# Sensors.net
KiCad netlist of a schematic drawn in Altium Designer
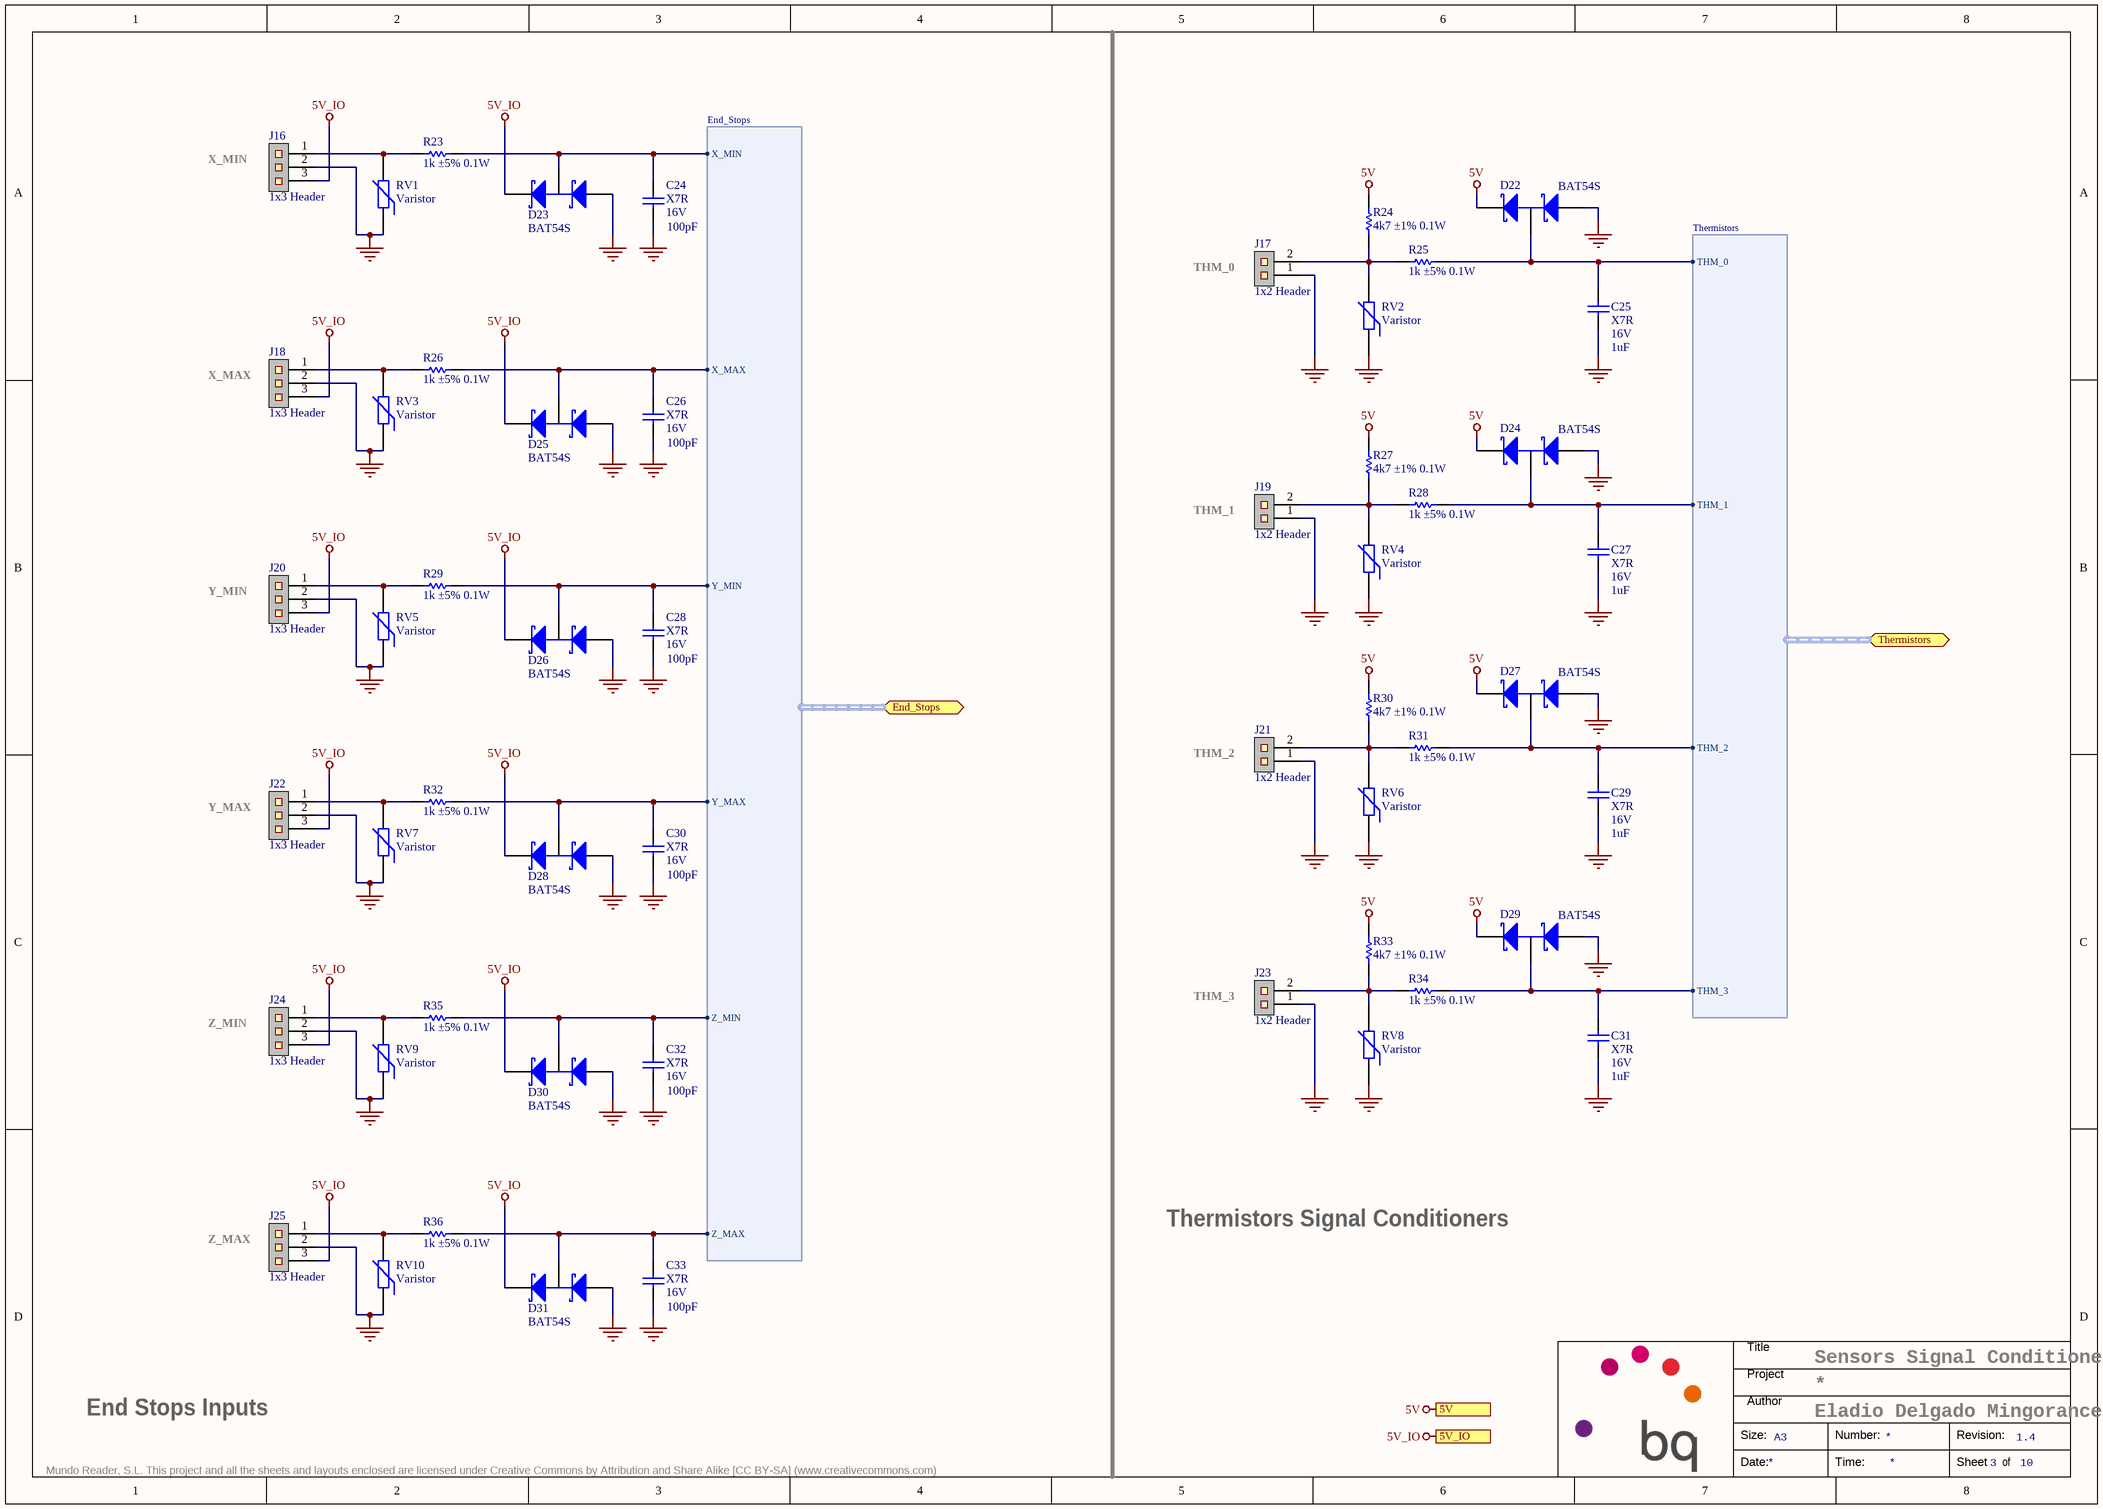
[diagram p0: Sensors.SchDoc]

(export (version "E")
  (design (tool "Eeschema 10.0.6"))
  (components
    (comp (ref "C24")
      (value "Capacitor")
      (footprint "C0603")
      (fields
        (field (name "DIELECTRIC") "X7R")
        (field (name "VOLTAGE") "16V")
        (field (name "CAPACITANCE") "100pF")
        (field (name "PART NUMBER") "C0603_100pF_16V_±10%")
        (field (name "TOLERANCE") "±10%")
        (field (name "MANUFACTURER") "Kemet")
      )
      (libsource (lib "Pasives_Capacitor_SMD") (part "Capacitor"))
    )
    (comp (ref "C25")
      (value "Capacitor")
      (footprint "C0603")
      (fields
        (field (name "DIELECTRIC") "X7R")
        (field (name "VOLTAGE") "16V")
        (field (name "CAPACITANCE") "1uF")
        (field (name "PART NUMBER") "C0603_1uF_16V_±10%_X7R")
        (field (name "TOLERANCE") "±10%")
        (field (name "MANUFACTURER") "TDK")
      )
      (libsource (lib "Pasives_Capacitor_SMD") (part "Capacitor"))
    )
    (comp (ref "C26")
      (value "Capacitor")
      (footprint "C0603")
      (fields
        (field (name "DIELECTRIC") "X7R")
        (field (name "VOLTAGE") "16V")
        (field (name "CAPACITANCE") "100pF")
        (field (name "PART NUMBER") "C0603_100pF_16V_±10%")
        (field (name "TOLERANCE") "±10%")
        (field (name "MANUFACTURER") "Kemet")
      )
      (libsource (lib "Pasives_Capacitor_SMD") (part "Capacitor"))
    )
    (comp (ref "C27")
      (value "Capacitor")
      (footprint "C0603")
      (fields
        (field (name "DIELECTRIC") "X7R")
        (field (name "VOLTAGE") "16V")
        (field (name "CAPACITANCE") "1uF")
        (field (name "PART NUMBER") "C0603_1uF_16V_±10%_X7R")
        (field (name "TOLERANCE") "±10%")
        (field (name "MANUFACTURER") "TDK")
      )
      (libsource (lib "Pasives_Capacitor_SMD") (part "Capacitor"))
    )
    (comp (ref "C28")
      (value "Capacitor")
      (footprint "C0603")
      (fields
        (field (name "DIELECTRIC") "X7R")
        (field (name "VOLTAGE") "16V")
        (field (name "CAPACITANCE") "100pF")
        (field (name "PART NUMBER") "C0603_100pF_16V_±10%")
        (field (name "TOLERANCE") "±10%")
        (field (name "MANUFACTURER") "Kemet")
      )
      (libsource (lib "Pasives_Capacitor_SMD") (part "Capacitor"))
    )
    (comp (ref "C29")
      (value "Capacitor")
      (footprint "C0603")
      (fields
        (field (name "DIELECTRIC") "X7R")
        (field (name "VOLTAGE") "16V")
        (field (name "CAPACITANCE") "1uF")
        (field (name "PART NUMBER") "C0603_1uF_16V_±10%_X7R")
        (field (name "TOLERANCE") "±10%")
        (field (name "MANUFACTURER") "TDK")
      )
      (libsource (lib "Pasives_Capacitor_SMD") (part "Capacitor"))
    )
    (comp (ref "C30")
      (value "Capacitor")
      (footprint "C0603")
      (fields
        (field (name "DIELECTRIC") "X7R")
        (field (name "VOLTAGE") "16V")
        (field (name "CAPACITANCE") "100pF")
        (field (name "PART NUMBER") "C0603_100pF_16V_±10%")
        (field (name "TOLERANCE") "±10%")
        (field (name "MANUFACTURER") "Kemet")
      )
      (libsource (lib "Pasives_Capacitor_SMD") (part "Capacitor"))
    )
    (comp (ref "C31")
      (value "Capacitor")
      (footprint "C0603")
      (fields
        (field (name "DIELECTRIC") "X7R")
        (field (name "VOLTAGE") "16V")
        (field (name "CAPACITANCE") "1uF")
        (field (name "PART NUMBER") "C0603_1uF_16V_±10%_X7R")
        (field (name "TOLERANCE") "±10%")
        (field (name "MANUFACTURER") "TDK")
      )
      (libsource (lib "Pasives_Capacitor_SMD") (part "Capacitor"))
    )
    (comp (ref "C32")
      (value "Capacitor")
      (footprint "C0603")
      (fields
        (field (name "DIELECTRIC") "X7R")
        (field (name "VOLTAGE") "16V")
        (field (name "CAPACITANCE") "100pF")
        (field (name "PART NUMBER") "C0603_100pF_16V_±10%")
        (field (name "TOLERANCE") "±10%")
        (field (name "MANUFACTURER") "Kemet")
      )
      (libsource (lib "Pasives_Capacitor_SMD") (part "Capacitor"))
    )
    (comp (ref "C33")
      (value "Capacitor")
      (footprint "C0603")
      (fields
        (field (name "DIELECTRIC") "X7R")
        (field (name "VOLTAGE") "16V")
        (field (name "CAPACITANCE") "100pF")
        (field (name "PART NUMBER") "C0603_100pF_16V_±10%")
        (field (name "TOLERANCE") "±10%")
        (field (name "MANUFACTURER") "Kemet")
      )
      (libsource (lib "Pasives_Capacitor_SMD") (part "Capacitor"))
    )
    (comp (ref "D22")
      (value "BAT54S")
      (footprint "SOT23-3")
      (description "Dual Schottky Diode")
      (fields (field (name "MANUFACTURER") "NXP"))
      (libsource (lib "Semiconductors_Diodes") (part "Dual Schottky"))
    )
    (comp (ref "D23")
      (value "BAT54S")
      (footprint "SOT23-3")
      (description "Dual Schottky Diode")
      (fields (field (name "MANUFACTURER") "NXP"))
      (libsource (lib "Semiconductors_Diodes") (part "Dual Schottky"))
    )
    (comp (ref "D24")
      (value "BAT54S")
      (footprint "SOT23-3")
      (description "Dual Schottky Diode")
      (fields (field (name "MANUFACTURER") "NXP"))
      (libsource (lib "Semiconductors_Diodes") (part "Dual Schottky"))
    )
    (comp (ref "D25")
      (value "BAT54S")
      (footprint "SOT23-3")
      (description "Dual Schottky Diode")
      (fields (field (name "MANUFACTURER") "NXP"))
      (libsource (lib "Semiconductors_Diodes") (part "Dual Schottky"))
    )
    (comp (ref "D26")
      (value "BAT54S")
      (footprint "SOT23-3")
      (description "Dual Schottky Diode")
      (fields (field (name "MANUFACTURER") "NXP"))
      (libsource (lib "Semiconductors_Diodes") (part "Dual Schottky"))
    )
    (comp (ref "D27")
      (value "BAT54S")
      (footprint "SOT23-3")
      (description "Dual Schottky Diode")
      (fields (field (name "MANUFACTURER") "NXP"))
      (libsource (lib "Semiconductors_Diodes") (part "Dual Schottky"))
    )
    (comp (ref "D28")
      (value "BAT54S")
      (footprint "SOT23-3")
      (description "Dual Schottky Diode")
      (fields (field (name "MANUFACTURER") "NXP"))
      (libsource (lib "Semiconductors_Diodes") (part "Dual Schottky"))
    )
    (comp (ref "D29")
      (value "BAT54S")
      (footprint "SOT23-3")
      (description "Dual Schottky Diode")
      (fields (field (name "MANUFACTURER") "NXP"))
      (libsource (lib "Semiconductors_Diodes") (part "Dual Schottky"))
    )
    (comp (ref "D30")
      (value "BAT54S")
      (footprint "SOT23-3")
      (description "Dual Schottky Diode")
      (fields (field (name "MANUFACTURER") "NXP"))
      (libsource (lib "Semiconductors_Diodes") (part "Dual Schottky"))
    )
    (comp (ref "D31")
      (value "BAT54S")
      (footprint "SOT23-3")
      (description "Dual Schottky Diode")
      (fields (field (name "MANUFACTURER") "NXP"))
      (libsource (lib "Semiconductors_Diodes") (part "Dual Schottky"))
    )
    (comp (ref "J16")
      (value "1x3 Header")
      (footprint "1x3 MTE Straight Header 2.54mm")
      (description "1x3 MTE Straight Header 2.54mm")
      (fields
        (field (name "PART NUMBER") "CON_MTE_HDR_THT2.54_3")
        (field (name "MANUFACTURER") "TE Connectivity")
      )
      (libsource (lib "Conectores_MTE_Header_2.54") (part "1x3 MTE Straight Header 2.54mm"))
    )
    (comp (ref "J17")
      (value "1x2 Header")
      (footprint "1x2 MTE Straight Header 2.54mm")
      (description "1x2 MTE Straight Header 2.54mm")
      (fields
        (field (name "PART NUMBER") "CON_MTE_HDR_THT2.54_2")
        (field (name "MANUFACTURER") "TE Connectivity")
      )
      (libsource (lib "Conectores_MTE_Header_2.54") (part "1x2 MTE Straight Header 2.54mm"))
    )
    (comp (ref "J18")
      (value "1x3 Header")
      (footprint "1x3 MTE Straight Header 2.54mm")
      (description "1x3 MTE Straight Header 2.54mm")
      (fields
        (field (name "PART NUMBER") "CON_MTE_HDR_THT2.54_3")
        (field (name "MANUFACTURER") "TE Connectivity")
      )
      (libsource (lib "Conectores_MTE_Header_2.54") (part "1x3 MTE Straight Header 2.54mm"))
    )
    (comp (ref "J19")
      (value "1x2 Header")
      (footprint "1x2 MTE Straight Header 2.54mm")
      (description "1x2 MTE Straight Header 2.54mm")
      (fields
        (field (name "PART NUMBER") "CON_MTE_HDR_THT2.54_2")
        (field (name "MANUFACTURER") "TE Connectivity")
      )
      (libsource (lib "Conectores_MTE_Header_2.54") (part "1x2 MTE Straight Header 2.54mm"))
    )
    (comp (ref "J20")
      (value "1x3 Header")
      (footprint "1x3 MTE Straight Header 2.54mm")
      (description "1x3 MTE Straight Header 2.54mm")
      (fields
        (field (name "PART NUMBER") "CON_MTE_HDR_THT2.54_3")
        (field (name "MANUFACTURER") "TE Connectivity")
      )
      (libsource (lib "Conectores_MTE_Header_2.54") (part "1x3 MTE Straight Header 2.54mm"))
    )
    (comp (ref "J21")
      (value "1x2 Header")
      (footprint "1x2 MTE Straight Header 2.54mm")
      (description "1x2 MTE Straight Header 2.54mm")
      (fields
        (field (name "PART NUMBER") "CON_MTE_HDR_THT2.54_2")
        (field (name "MANUFACTURER") "TE Connectivity")
      )
      (libsource (lib "Conectores_MTE_Header_2.54") (part "1x2 MTE Straight Header 2.54mm"))
    )
    (comp (ref "J22")
      (value "1x3 Header")
      (footprint "1x3 MTE Straight Header 2.54mm")
      (description "1x3 MTE Straight Header 2.54mm")
      (fields
        (field (name "PART NUMBER") "CON_MTE_HDR_THT2.54_3")
        (field (name "MANUFACTURER") "TE Connectivity")
      )
      (libsource (lib "Conectores_MTE_Header_2.54") (part "1x3 MTE Straight Header 2.54mm"))
    )
    (comp (ref "J23")
      (value "1x2 Header")
      (footprint "1x2 MTE Straight Header 2.54mm")
      (description "1x2 MTE Straight Header 2.54mm")
      (fields
        (field (name "PART NUMBER") "CON_MTE_HDR_THT2.54_2")
        (field (name "MANUFACTURER") "TE Connectivity")
      )
      (libsource (lib "Conectores_MTE_Header_2.54") (part "1x2 MTE Straight Header 2.54mm"))
    )
    (comp (ref "J24")
      (value "1x3 Header")
      (footprint "1x3 MTE Straight Header 2.54mm")
      (description "1x3 MTE Straight Header 2.54mm")
      (fields
        (field (name "PART NUMBER") "CON_MTE_HDR_THT2.54_3")
        (field (name "MANUFACTURER") "TE Connectivity")
      )
      (libsource (lib "Conectores_MTE_Header_2.54") (part "1x3 MTE Straight Header 2.54mm"))
    )
    (comp (ref "J25")
      (value "1x3 Header")
      (footprint "1x3 MTE Straight Header 2.54mm")
      (description "1x3 MTE Straight Header 2.54mm")
      (fields
        (field (name "PART NUMBER") "CON_MTE_HDR_THT2.54_3")
        (field (name "MANUFACTURER") "TE Connectivity")
      )
      (libsource (lib "Conectores_MTE_Header_2.54") (part "1x3 MTE Straight Header 2.54mm"))
    )
    (comp (ref "R23")
      (value "1k ±5% 0.1W")
      (footprint "R0603")
      (description "Resistor")
      (fields (field (name "TOLERANCE") "±5%") (field (name "POWER") "0.1W"))
      (libsource (lib "Pasives_Resistor_SMD") (part "Resistor"))
    )
    (comp (ref "R24")
      (value "4k7 ±1% 0.1W")
      (footprint "R0603")
      (description "Resistor")
      (fields (field (name "TOLERANCE") "±1%") (field (name "POWER") "0.1W"))
      (libsource (lib "Pasives_Resistor_SMD") (part "Resistor"))
    )
    (comp (ref "R25")
      (value "1k ±5% 0.1W")
      (footprint "R0603")
      (description "Resistor")
      (fields (field (name "TOLERANCE") "±5%") (field (name "POWER") "0.1W"))
      (libsource (lib "Pasives_Resistor_SMD") (part "Resistor"))
    )
    (comp (ref "R26")
      (value "1k ±5% 0.1W")
      (footprint "R0603")
      (description "Resistor")
      (fields (field (name "TOLERANCE") "±5%") (field (name "POWER") "0.1W"))
      (libsource (lib "Pasives_Resistor_SMD") (part "Resistor"))
    )
    (comp (ref "R27")
      (value "4k7 ±1% 0.1W")
      (footprint "R0603")
      (description "Resistor")
      (fields (field (name "TOLERANCE") "±1%") (field (name "POWER") "0.1W"))
      (libsource (lib "Pasives_Resistor_SMD") (part "Resistor"))
    )
    (comp (ref "R28")
      (value "1k ±5% 0.1W")
      (footprint "R0603")
      (description "Resistor")
      (fields (field (name "TOLERANCE") "±5%") (field (name "POWER") "0.1W"))
      (libsource (lib "Pasives_Resistor_SMD") (part "Resistor"))
    )
    (comp (ref "R29")
      (value "1k ±5% 0.1W")
      (footprint "R0603")
      (description "Resistor")
      (fields (field (name "TOLERANCE") "±5%") (field (name "POWER") "0.1W"))
      (libsource (lib "Pasives_Resistor_SMD") (part "Resistor"))
    )
    (comp (ref "R30")
      (value "4k7 ±1% 0.1W")
      (footprint "R0603")
      (description "Resistor")
      (fields (field (name "TOLERANCE") "±1%") (field (name "POWER") "0.1W"))
      (libsource (lib "Pasives_Resistor_SMD") (part "Resistor"))
    )
    (comp (ref "R31")
      (value "1k ±5% 0.1W")
      (footprint "R0603")
      (description "Resistor")
      (fields (field (name "TOLERANCE") "±5%") (field (name "POWER") "0.1W"))
      (libsource (lib "Pasives_Resistor_SMD") (part "Resistor"))
    )
    (comp (ref "R32")
      (value "1k ±5% 0.1W")
      (footprint "R0603")
      (description "Resistor")
      (fields (field (name "TOLERANCE") "±5%") (field (name "POWER") "0.1W"))
      (libsource (lib "Pasives_Resistor_SMD") (part "Resistor"))
    )
    (comp (ref "R33")
      (value "4k7 ±1% 0.1W")
      (footprint "R0603")
      (description "Resistor")
      (fields (field (name "TOLERANCE") "±1%") (field (name "POWER") "0.1W"))
      (libsource (lib "Pasives_Resistor_SMD") (part "Resistor"))
    )
    (comp (ref "R34")
      (value "1k ±5% 0.1W")
      (footprint "R0603")
      (description "Resistor")
      (fields (field (name "TOLERANCE") "±5%") (field (name "POWER") "0.1W"))
      (libsource (lib "Pasives_Resistor_SMD") (part "Resistor"))
    )
    (comp (ref "R35")
      (value "1k ±5% 0.1W")
      (footprint "R0603")
      (description "Resistor")
      (fields (field (name "TOLERANCE") "±5%") (field (name "POWER") "0.1W"))
      (libsource (lib "Pasives_Resistor_SMD") (part "Resistor"))
    )
    (comp (ref "R36")
      (value "1k ±5% 0.1W")
      (footprint "R0603")
      (description "Resistor")
      (fields (field (name "TOLERANCE") "±5%") (field (name "POWER") "0.1W"))
      (libsource (lib "Pasives_Resistor_SMD") (part "Resistor"))
    )
    (comp (ref "RV1")
      (value "Varistor")
      (footprint "RV0603")
      (fields
        (field (name "PART NUMBER") "Varistor 14V SMD")
        (field (name "VOLTAGE") "14")
        (field (name "MANUFACTURER") "Cooper Bussmann")
      )
      (libsource (lib "Protection") (part "Varistor"))
    )
    (comp (ref "RV2")
      (value "Varistor")
      (footprint "RV0603")
      (fields
        (field (name "PART NUMBER") "Varistor 14V SMD")
        (field (name "VOLTAGE") "14")
        (field (name "MANUFACTURER") "Cooper Bussmann")
      )
      (libsource (lib "Protection") (part "Varistor"))
    )
    (comp (ref "RV3")
      (value "Varistor")
      (footprint "RV0603")
      (fields
        (field (name "PART NUMBER") "Varistor 14V SMD")
        (field (name "VOLTAGE") "14")
        (field (name "MANUFACTURER") "Cooper Bussmann")
      )
      (libsource (lib "Protection") (part "Varistor"))
    )
    (comp (ref "RV4")
      (value "Varistor")
      (footprint "RV0603")
      (fields
        (field (name "PART NUMBER") "Varistor 14V SMD")
        (field (name "VOLTAGE") "14")
        (field (name "MANUFACTURER") "Cooper Bussmann")
      )
      (libsource (lib "Protection") (part "Varistor"))
    )
    (comp (ref "RV5")
      (value "Varistor")
      (footprint "RV0603")
      (fields
        (field (name "PART NUMBER") "Varistor 14V SMD")
        (field (name "VOLTAGE") "14")
        (field (name "MANUFACTURER") "Cooper Bussmann")
      )
      (libsource (lib "Protection") (part "Varistor"))
    )
    (comp (ref "RV6")
      (value "Varistor")
      (footprint "RV0603")
      (fields
        (field (name "PART NUMBER") "Varistor 14V SMD")
        (field (name "VOLTAGE") "14")
        (field (name "MANUFACTURER") "Cooper Bussmann")
      )
      (libsource (lib "Protection") (part "Varistor"))
    )
    (comp (ref "RV7")
      (value "Varistor")
      (footprint "RV0603")
      (fields
        (field (name "PART NUMBER") "Varistor 14V SMD")
        (field (name "VOLTAGE") "14")
        (field (name "MANUFACTURER") "Cooper Bussmann")
      )
      (libsource (lib "Protection") (part "Varistor"))
    )
    (comp (ref "RV8")
      (value "Varistor")
      (footprint "RV0603")
      (fields
        (field (name "PART NUMBER") "Varistor 14V SMD")
        (field (name "VOLTAGE") "14")
        (field (name "MANUFACTURER") "Cooper Bussmann")
      )
      (libsource (lib "Protection") (part "Varistor"))
    )
    (comp (ref "RV9")
      (value "Varistor")
      (footprint "RV0603")
      (fields
        (field (name "PART NUMBER") "Varistor 14V SMD")
        (field (name "VOLTAGE") "14")
        (field (name "MANUFACTURER") "Cooper Bussmann")
      )
      (libsource (lib "Protection") (part "Varistor"))
    )
    (comp (ref "RV10")
      (value "Varistor")
      (footprint "RV0603")
      (fields
        (field (name "PART NUMBER") "Varistor 14V SMD")
        (field (name "VOLTAGE") "14")
        (field (name "MANUFACTURER") "Cooper Bussmann")
      )
      (libsource (lib "Protection") (part "Varistor"))
    )
  )
  (nets
    (net (code "5") (name "5V") (class "Default")
      (node (ref "D22") (pin "2") (pinfunction "K_2") (pintype "passive"))
      (node (ref "D24") (pin "2") (pinfunction "K_2") (pintype "passive"))
      (node (ref "D27") (pin "2") (pinfunction "K_2") (pintype "passive"))
      (node (ref "D29") (pin "2") (pinfunction "K_2") (pintype "passive"))
      (node (ref "R24") (pin "2") (pinfunction "2_2") (pintype "passive"))
      (node (ref "R27") (pin "2") (pinfunction "2_2") (pintype "passive"))
      (node (ref "R30") (pin "2") (pinfunction "2_2") (pintype "passive"))
      (node (ref "R33") (pin "2") (pinfunction "2_2") (pintype "passive"))
    )
    (net (code "6") (name "5V_IO") (class "Default")
      (node (ref "D23") (pin "2") (pinfunction "K_2") (pintype "passive"))
      (node (ref "D25") (pin "2") (pinfunction "K_2") (pintype "passive"))
      (node (ref "D26") (pin "2") (pinfunction "K_2") (pintype "passive"))
      (node (ref "D28") (pin "2") (pinfunction "K_2") (pintype "passive"))
      (node (ref "D30") (pin "2") (pinfunction "K_2") (pintype "passive"))
      (node (ref "D31") (pin "2") (pinfunction "K_2") (pintype "passive"))
      (node (ref "J16") (pin "3") (pinfunction "3_3") (pintype "passive"))
      (node (ref "J18") (pin "3") (pinfunction "3_3") (pintype "passive"))
      (node (ref "J20") (pin "3") (pinfunction "3_3") (pintype "passive"))
      (node (ref "J22") (pin "3") (pinfunction "3_3") (pintype "passive"))
      (node (ref "J24") (pin "3") (pinfunction "3_3") (pintype "passive"))
      (node (ref "J25") (pin "3") (pinfunction "3_3") (pintype "passive"))
    )
    (net (code "7") (name "GND") (class "Default")
      (node (ref "C24") (pin "1") (pinfunction "1_1") (pintype "passive"))
      (node (ref "C25") (pin "1") (pinfunction "1_1") (pintype "passive"))
      (node (ref "C26") (pin "1") (pinfunction "1_1") (pintype "passive"))
      (node (ref "C27") (pin "1") (pinfunction "1_1") (pintype "passive"))
      (node (ref "C28") (pin "1") (pinfunction "1_1") (pintype "passive"))
      (node (ref "C29") (pin "1") (pinfunction "1_1") (pintype "passive"))
      (node (ref "C30") (pin "1") (pinfunction "1_1") (pintype "passive"))
      (node (ref "C31") (pin "1") (pinfunction "1_1") (pintype "passive"))
      (node (ref "C32") (pin "1") (pinfunction "1_1") (pintype "passive"))
      (node (ref "C33") (pin "1") (pinfunction "1_1") (pintype "passive"))
      (node (ref "D22") (pin "1") (pinfunction "A_1") (pintype "passive"))
      (node (ref "D23") (pin "1") (pinfunction "A_1") (pintype "passive"))
      (node (ref "D24") (pin "1") (pinfunction "A_1") (pintype "passive"))
      (node (ref "D25") (pin "1") (pinfunction "A_1") (pintype "passive"))
      (node (ref "D26") (pin "1") (pinfunction "A_1") (pintype "passive"))
      (node (ref "D27") (pin "1") (pinfunction "A_1") (pintype "passive"))
      (node (ref "D28") (pin "1") (pinfunction "A_1") (pintype "passive"))
      (node (ref "D29") (pin "1") (pinfunction "A_1") (pintype "passive"))
      (node (ref "D30") (pin "1") (pinfunction "A_1") (pintype "passive"))
      (node (ref "D31") (pin "1") (pinfunction "A_1") (pintype "passive"))
      (node (ref "J16") (pin "2") (pinfunction "2_2") (pintype "passive"))
      (node (ref "J17") (pin "1") (pinfunction "1_1") (pintype "passive"))
      (node (ref "J18") (pin "2") (pinfunction "2_2") (pintype "passive"))
      (node (ref "J19") (pin "1") (pinfunction "1_1") (pintype "passive"))
      (node (ref "J20") (pin "2") (pinfunction "2_2") (pintype "passive"))
      (node (ref "J21") (pin "1") (pinfunction "1_1") (pintype "passive"))
      (node (ref "J22") (pin "2") (pinfunction "2_2") (pintype "passive"))
      (node (ref "J23") (pin "1") (pinfunction "1_1") (pintype "passive"))
      (node (ref "J24") (pin "2") (pinfunction "2_2") (pintype "passive"))
      (node (ref "J25") (pin "2") (pinfunction "2_2") (pintype "passive"))
      (node (ref "RV1") (pin "1") (pinfunction "1_1") (pintype "passive"))
      (node (ref "RV10") (pin "1") (pinfunction "1_1") (pintype "passive"))
      (node (ref "RV2") (pin "1") (pinfunction "1_1") (pintype "passive"))
      (node (ref "RV3") (pin "1") (pinfunction "1_1") (pintype "passive"))
      (node (ref "RV4") (pin "1") (pinfunction "1_1") (pintype "passive"))
      (node (ref "RV5") (pin "1") (pinfunction "1_1") (pintype "passive"))
      (node (ref "RV6") (pin "1") (pinfunction "1_1") (pintype "passive"))
      (node (ref "RV7") (pin "1") (pinfunction "1_1") (pintype "passive"))
      (node (ref "RV8") (pin "1") (pinfunction "1_1") (pintype "passive"))
      (node (ref "RV9") (pin "1") (pinfunction "1_1") (pintype "passive"))
    )
    (net (code "8") (name "Net-(C24-Pad2)") (class "Default")
      (node (ref "C24") (pin "2") (pinfunction "2_2") (pintype "passive"))
      (node (ref "D23") (pin "3") (pinfunction "K_3") (pintype "passive"))
      (node (ref "R23") (pin "2") (pinfunction "2_2") (pintype "passive"))
    )
    (net (code "9") (name "Net-(C25-Pad2)") (class "Default")
      (node (ref "C25") (pin "2") (pinfunction "2_2") (pintype "passive"))
      (node (ref "D22") (pin "3") (pinfunction "K_3") (pintype "passive"))
      (node (ref "R25") (pin "2") (pinfunction "2_2") (pintype "passive"))
    )
    (net (code "10") (name "Net-(C26-Pad2)") (class "Default")
      (node (ref "C26") (pin "2") (pinfunction "2_2") (pintype "passive"))
      (node (ref "D25") (pin "3") (pinfunction "K_3") (pintype "passive"))
      (node (ref "R26") (pin "2") (pinfunction "2_2") (pintype "passive"))
    )
    (net (code "11") (name "Net-(C27-Pad2)") (class "Default")
      (node (ref "C27") (pin "2") (pinfunction "2_2") (pintype "passive"))
      (node (ref "D24") (pin "3") (pinfunction "K_3") (pintype "passive"))
      (node (ref "R28") (pin "2") (pinfunction "2_2") (pintype "passive"))
    )
    (net (code "12") (name "Net-(C28-Pad2)") (class "Default")
      (node (ref "C28") (pin "2") (pinfunction "2_2") (pintype "passive"))
      (node (ref "D26") (pin "3") (pinfunction "K_3") (pintype "passive"))
      (node (ref "R29") (pin "2") (pinfunction "2_2") (pintype "passive"))
    )
    (net (code "13") (name "Net-(C29-Pad2)") (class "Default")
      (node (ref "C29") (pin "2") (pinfunction "2_2") (pintype "passive"))
      (node (ref "D27") (pin "3") (pinfunction "K_3") (pintype "passive"))
      (node (ref "R31") (pin "2") (pinfunction "2_2") (pintype "passive"))
    )
    (net (code "14") (name "Net-(C30-Pad2)") (class "Default")
      (node (ref "C30") (pin "2") (pinfunction "2_2") (pintype "passive"))
      (node (ref "D28") (pin "3") (pinfunction "K_3") (pintype "passive"))
      (node (ref "R32") (pin "2") (pinfunction "2_2") (pintype "passive"))
    )
    (net (code "15") (name "Net-(C31-Pad2)") (class "Default")
      (node (ref "C31") (pin "2") (pinfunction "2_2") (pintype "passive"))
      (node (ref "D29") (pin "3") (pinfunction "K_3") (pintype "passive"))
      (node (ref "R34") (pin "2") (pinfunction "2_2") (pintype "passive"))
    )
    (net (code "16") (name "Net-(C32-Pad2)") (class "Default")
      (node (ref "C32") (pin "2") (pinfunction "2_2") (pintype "passive"))
      (node (ref "D30") (pin "3") (pinfunction "K_3") (pintype "passive"))
      (node (ref "R35") (pin "2") (pinfunction "2_2") (pintype "passive"))
    )
    (net (code "17") (name "Net-(C33-Pad2)") (class "Default")
      (node (ref "C33") (pin "2") (pinfunction "2_2") (pintype "passive"))
      (node (ref "D31") (pin "3") (pinfunction "K_3") (pintype "passive"))
      (node (ref "R36") (pin "2") (pinfunction "2_2") (pintype "passive"))
    )
    (net (code "18") (name "Net-(J16-Pad1)") (class "Default")
      (node (ref "J16") (pin "1") (pinfunction "1_1") (pintype "passive"))
      (node (ref "R23") (pin "1") (pinfunction "1_1") (pintype "passive"))
      (node (ref "RV1") (pin "2") (pinfunction "2_2") (pintype "passive"))
    )
    (net (code "19") (name "Net-(J17-Pad2)") (class "Default")
      (node (ref "J17") (pin "2") (pinfunction "2_2") (pintype "passive"))
      (node (ref "R24") (pin "1") (pinfunction "1_1") (pintype "passive"))
      (node (ref "R25") (pin "1") (pinfunction "1_1") (pintype "passive"))
      (node (ref "RV2") (pin "2") (pinfunction "2_2") (pintype "passive"))
    )
    (net (code "20") (name "Net-(J18-Pad1)") (class "Default")
      (node (ref "J18") (pin "1") (pinfunction "1_1") (pintype "passive"))
      (node (ref "R26") (pin "1") (pinfunction "1_1") (pintype "passive"))
      (node (ref "RV3") (pin "2") (pinfunction "2_2") (pintype "passive"))
    )
    (net (code "21") (name "Net-(J19-Pad2)") (class "Default")
      (node (ref "J19") (pin "2") (pinfunction "2_2") (pintype "passive"))
      (node (ref "R27") (pin "1") (pinfunction "1_1") (pintype "passive"))
      (node (ref "R28") (pin "1") (pinfunction "1_1") (pintype "passive"))
      (node (ref "RV4") (pin "2") (pinfunction "2_2") (pintype "passive"))
    )
    (net (code "22") (name "Net-(J20-Pad1)") (class "Default")
      (node (ref "J20") (pin "1") (pinfunction "1_1") (pintype "passive"))
      (node (ref "R29") (pin "1") (pinfunction "1_1") (pintype "passive"))
      (node (ref "RV5") (pin "2") (pinfunction "2_2") (pintype "passive"))
    )
    (net (code "23") (name "Net-(J21-Pad2)") (class "Default")
      (node (ref "J21") (pin "2") (pinfunction "2_2") (pintype "passive"))
      (node (ref "R30") (pin "1") (pinfunction "1_1") (pintype "passive"))
      (node (ref "R31") (pin "1") (pinfunction "1_1") (pintype "passive"))
      (node (ref "RV6") (pin "2") (pinfunction "2_2") (pintype "passive"))
    )
    (net (code "24") (name "Net-(J22-Pad1)") (class "Default")
      (node (ref "J22") (pin "1") (pinfunction "1_1") (pintype "passive"))
      (node (ref "R32") (pin "1") (pinfunction "1_1") (pintype "passive"))
      (node (ref "RV7") (pin "2") (pinfunction "2_2") (pintype "passive"))
    )
    (net (code "25") (name "Net-(J23-Pad2)") (class "Default")
      (node (ref "J23") (pin "2") (pinfunction "2_2") (pintype "passive"))
      (node (ref "R33") (pin "1") (pinfunction "1_1") (pintype "passive"))
      (node (ref "R34") (pin "1") (pinfunction "1_1") (pintype "passive"))
      (node (ref "RV8") (pin "2") (pinfunction "2_2") (pintype "passive"))
    )
    (net (code "26") (name "Net-(J24-Pad1)") (class "Default")
      (node (ref "J24") (pin "1") (pinfunction "1_1") (pintype "passive"))
      (node (ref "R35") (pin "1") (pinfunction "1_1") (pintype "passive"))
      (node (ref "RV9") (pin "2") (pinfunction "2_2") (pintype "passive"))
    )
    (net (code "27") (name "Net-(J25-Pad1)") (class "Default")
      (node (ref "J25") (pin "1") (pinfunction "1_1") (pintype "passive"))
      (node (ref "R36") (pin "1") (pinfunction "1_1") (pintype "passive"))
      (node (ref "RV10") (pin "2") (pinfunction "2_2") (pintype "passive"))
    )
  )
)
